# BG_IO_Programming_Schematic.net
KiCad netlist of a schematic drawn in Altium Designer
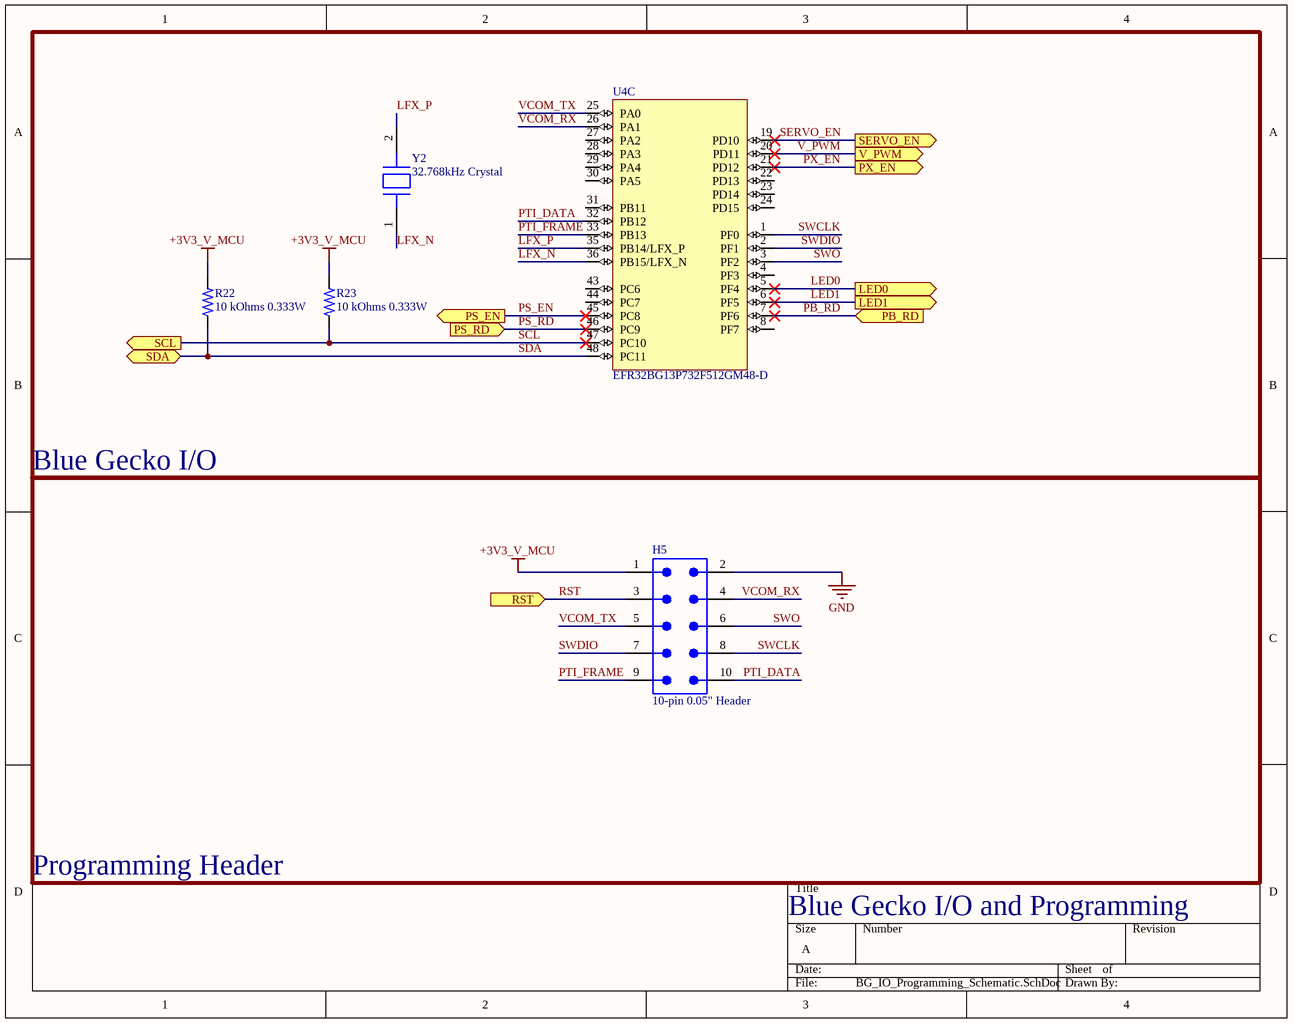
[diagram p0: BG_IO_Programming_Schematic.SchDoc]

(export (version "E")
  (design (tool "Eeschema 10.0.6"))
  (components
    (comp (ref "H5")
      (value "10-pin 0.05\" Header")
      (footprint "FTSH-105-01-XXX-DV-K")
      (description "Conn Unshrouded Header HDR 10 POS 1.27mm Solder ST Top Entry SMD Tube")
      (fields
        (field (name "MANUFACTURER") "Samtec")
        (field (name "MANUFACTURER PART NUMBER") "FTSH-105-01-LM-DV-K")
      )
      (libsource (lib "PartsLib") (part "FTSH-105-01-LM-DV-K"))
    )
    (comp (ref "R22")
      (value "10 kOhms 0.333W")
      (footprint "RESC0603X06N")
      (description "Res Thick Film 0603 10K Ohm 1% 0.33W(1/3W) ±100ppm/°C Pad SMD Automotive T/R")
      (fields
        (field (name "MANUFACTURER") "Vishay")
        (field (name "MANUFACTURER PART NUMBER") "CRCW060310K0FKEAHP")
      )
      (libsource (lib "PartsLib") (part "CRCW060310K0FKEAHP"))
    )
    (comp (ref "R23")
      (value "10 kOhms 0.333W")
      (footprint "RESC0603X06N")
      (description "Res Thick Film 0603 10K Ohm 1% 0.33W(1/3W) ±100ppm/°C Pad SMD Automotive T/R")
      (fields
        (field (name "MANUFACTURER") "Vishay")
        (field (name "MANUFACTURER PART NUMBER") "CRCW060310K0FKEAHP")
      )
      (libsource (lib "PartsLib") (part "CRCW060310K0FKEAHP"))
    )
    (comp (ref "U4")
      (value "EFR32BG13P732F512GM48-D")
      (footprint "48-QFN_7x7")
      (description "Blue Gecko QFN48 2.4 G 19 dB BLE/Proprietary 512 kB 64 kB(RAM) 31GPIO")
      (fields (field (name "MANUFACTURER") "Silicon Labs"))
      (libsource (lib "PartsLib") (part "EFR32BG13P732F512GM48-D"))
    )
    (comp (ref "Y2")
      (value "32.768kHz Crystal")
      (footprint "DFN153P160X50-2N")
      (description "CRYSTAL 32.768KHZ 7PF SMD")
      (fields
        (field (name "MANUFACTURER") "Abracon")
        (field (name "MANUFACTURER PART NUMBER") "ABS05-32.768KHZ-7-T")
      )
      (libsource (lib "PartsLib") (part "ABS05-32.768KHZ-7-T"))
    )
  )
  (nets
    (net (code "1") (name "+3V3_V_MCU") (class "Default")
      (node (ref "H5") (pin "1") (pinfunction "1_1") (pintype "passive"))
      (node (ref "R22") (pin "2") (pinfunction "2_2") (pintype "passive"))
      (node (ref "R23") (pin "2") (pinfunction "2_2") (pintype "passive"))
    )
    (net (code "2") (name "/LED0") (class "Default")
      (node (ref "U4") (pin "5") (pinfunction "PF4_5") (pintype "bidirectional+no_connect"))
    )
    (net (code "3") (name "/LED1") (class "Default")
      (node (ref "U4") (pin "6") (pinfunction "PF5_6") (pintype "bidirectional+no_connect"))
    )
    (net (code "4") (name "/LFX_N") (class "Default")
      (node (ref "U4") (pin "36") (pinfunction "PB15/LFX_N_36") (pintype "bidirectional"))
      (node (ref "Y2") (pin "1") (pinfunction "1_1") (pintype "passive"))
    )
    (net (code "5") (name "/LFX_P") (class "Default")
      (node (ref "U4") (pin "35") (pinfunction "PB14/LFX_P_35") (pintype "bidirectional"))
      (node (ref "Y2") (pin "2") (pinfunction "2_2") (pintype "passive"))
    )
    (net (code "6") (name "/PB_RD") (class "Default")
      (node (ref "U4") (pin "7") (pinfunction "PF6_7") (pintype "bidirectional+no_connect"))
    )
    (net (code "7") (name "/PS_EN") (class "Default")
      (node (ref "U4") (pin "45") (pinfunction "PC8_45") (pintype "bidirectional+no_connect"))
    )
    (net (code "8") (name "/PS_RD") (class "Default")
      (node (ref "U4") (pin "46") (pinfunction "PC9_46") (pintype "bidirectional+no_connect"))
    )
    (net (code "9") (name "/PTI_DATA") (class "Default")
      (node (ref "H5") (pin "10") (pinfunction "10_10") (pintype "passive"))
      (node (ref "U4") (pin "32") (pinfunction "PB12_32") (pintype "bidirectional"))
    )
    (net (code "10") (name "/PTI_FRAME") (class "Default")
      (node (ref "H5") (pin "9") (pinfunction "9_9") (pintype "passive"))
      (node (ref "U4") (pin "33") (pinfunction "PB13_33") (pintype "bidirectional"))
    )
    (net (code "11") (name "/PX_EN") (class "Default")
      (node (ref "U4") (pin "21") (pinfunction "PD12_21") (pintype "bidirectional+no_connect"))
    )
    (net (code "12") (name "/RST") (class "Default")
      (node (ref "H5") (pin "3") (pinfunction "3_3") (pintype "passive"))
    )
    (net (code "13") (name "/SCL") (class "Default")
      (node (ref "R23") (pin "1") (pinfunction "1_1") (pintype "passive"))
      (node (ref "U4") (pin "47") (pinfunction "PC10_47") (pintype "bidirectional"))
    )
    (net (code "14") (name "/SDA") (class "Default")
      (node (ref "R22") (pin "1") (pinfunction "1_1") (pintype "passive"))
      (node (ref "U4") (pin "48") (pinfunction "PC11_48") (pintype "bidirectional"))
    )
    (net (code "15") (name "/SERVO_EN") (class "Default")
      (node (ref "U4") (pin "19") (pinfunction "PD10_19") (pintype "bidirectional+no_connect"))
    )
    (net (code "16") (name "/SWCLK") (class "Default")
      (node (ref "H5") (pin "8") (pinfunction "8_8") (pintype "passive"))
      (node (ref "U4") (pin "1") (pinfunction "PF0_1") (pintype "bidirectional"))
    )
    (net (code "17") (name "/SWDIO") (class "Default")
      (node (ref "H5") (pin "7") (pinfunction "7_7") (pintype "passive"))
      (node (ref "U4") (pin "2") (pinfunction "PF1_2") (pintype "bidirectional"))
    )
    (net (code "18") (name "/SWO") (class "Default")
      (node (ref "H5") (pin "6") (pinfunction "6_6") (pintype "passive"))
      (node (ref "U4") (pin "3") (pinfunction "PF2_3") (pintype "bidirectional"))
    )
    (net (code "19") (name "/VCOM_RX") (class "Default")
      (node (ref "H5") (pin "4") (pinfunction "4_4") (pintype "passive"))
      (node (ref "U4") (pin "26") (pinfunction "PA1_26") (pintype "bidirectional"))
    )
    (net (code "20") (name "/VCOM_TX") (class "Default")
      (node (ref "H5") (pin "5") (pinfunction "5_5") (pintype "passive"))
      (node (ref "U4") (pin "25") (pinfunction "PA0_25") (pintype "bidirectional"))
    )
    (net (code "21") (name "/V_PWM") (class "Default")
      (node (ref "U4") (pin "20") (pinfunction "PD11_20") (pintype "bidirectional+no_connect"))
    )
    (net (code "22") (name "GND") (class "Default")
      (node (ref "H5") (pin "2") (pinfunction "2_2") (pintype "passive"))
    )
    (net (code "23") (name "unconnected-(U4C-PA2-Pad27)") (class "Default")
      (node (ref "U4") (pin "27") (pinfunction "PA2_27") (pintype "bidirectional"))
    )
    (net (code "24") (name "unconnected-(U4C-PA3-Pad28)") (class "Default")
      (node (ref "U4") (pin "28") (pinfunction "PA3_28") (pintype "bidirectional"))
    )
    (net (code "25") (name "unconnected-(U4C-PA4-Pad29)") (class "Default")
      (node (ref "U4") (pin "29") (pinfunction "PA4_29") (pintype "bidirectional"))
    )
    (net (code "26") (name "unconnected-(U4C-PA5-Pad30)") (class "Default")
      (node (ref "U4") (pin "30") (pinfunction "PA5_30") (pintype "bidirectional"))
    )
    (net (code "27") (name "unconnected-(U4C-PB11-Pad31)") (class "Default")
      (node (ref "U4") (pin "31") (pinfunction "PB11_31") (pintype "bidirectional"))
    )
    (net (code "28") (name "unconnected-(U4C-PC6-Pad43)") (class "Default")
      (node (ref "U4") (pin "43") (pinfunction "PC6_43") (pintype "bidirectional"))
    )
    (net (code "29") (name "unconnected-(U4C-PC7-Pad44)") (class "Default")
      (node (ref "U4") (pin "44") (pinfunction "PC7_44") (pintype "bidirectional"))
    )
    (net (code "30") (name "unconnected-(U4C-PD13-Pad22)") (class "Default")
      (node (ref "U4") (pin "22") (pinfunction "PD13_22") (pintype "bidirectional"))
    )
    (net (code "31") (name "unconnected-(U4C-PD14-Pad23)") (class "Default")
      (node (ref "U4") (pin "23") (pinfunction "PD14_23") (pintype "bidirectional"))
    )
    (net (code "32") (name "unconnected-(U4C-PD15-Pad24)") (class "Default")
      (node (ref "U4") (pin "24") (pinfunction "PD15_24") (pintype "bidirectional"))
    )
    (net (code "33") (name "unconnected-(U4C-PF3-Pad4)") (class "Default")
      (node (ref "U4") (pin "4") (pinfunction "PF3_4") (pintype "bidirectional"))
    )
    (net (code "34") (name "unconnected-(U4C-PF7-Pad8)") (class "Default")
      (node (ref "U4") (pin "8") (pinfunction "PF7_8") (pintype "bidirectional"))
    )
  )
)
